# esp8266-01relayfabab-CONPLANOMASA.net
KiCad netlist of a schematic drawn in EAGLE
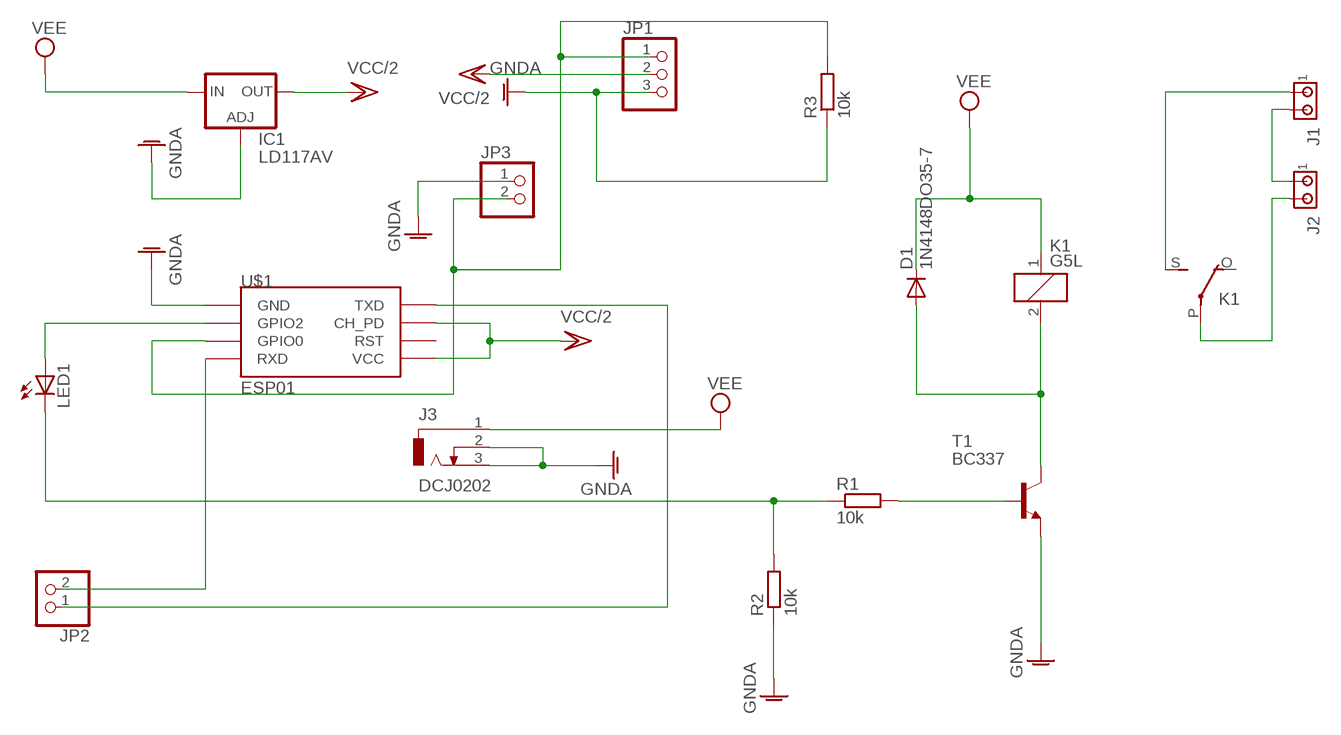
[diagram p0: schematic, sheet 1]

(export (version "E")
  (design (tool "Eeschema 10.0.6"))
  (components
    (comp (ref "D1")
      (value "1N4148DO35-7")
      (footprint "eagle-import:DO35-7")
      (libsource (lib "eagle-import") (part "1N4148DO35-7"))
    )
    (comp (ref "IC1")
      (value "LD117AV")
      (footprint "eagle-import:TO220L1")
      (libsource (lib "eagle-import") (part "LD117A?V"))
    )
    (comp (ref "J1")
      (value "MTA02-156")
      (footprint "eagle-import:1X2MTA")
      (libsource (lib "eagle-import") (part "MTA02-156"))
    )
    (comp (ref "J2")
      (value "MTA02-156")
      (footprint "eagle-import:1X2MTA")
      (libsource (lib "eagle-import") (part "MTA02-156"))
    )
    (comp (ref "J3")
      (value "DCJ0202")
      (footprint "eagle-import:DCJ0202")
      (libsource (lib "eagle-import") (part "DCJ0202"))
    )
    (comp (ref "JP1")
      (value "PINHD-1X3")
      (footprint "eagle-import:1X03")
      (libsource (lib "eagle-import") (part "PINHD-1X3"))
    )
    (comp (ref "JP2")
      (value "PINHD-1X2")
      (footprint "eagle-import:1X02")
      (libsource (lib "eagle-import") (part "PINHD-1X2"))
    )
    (comp (ref "JP3")
      (value "PINHD-1X2")
      (footprint "eagle-import:1X02")
      (libsource (lib "eagle-import") (part "PINHD-1X2"))
    )
    (comp (ref "K1")
      (value "G5L")
      (footprint "eagle-import:G5LE")
      (libsource (lib "eagle-import") (part "G5L"))
    )
    (comp (ref "LED1")
      (value "LED5MM")
      (footprint "eagle-import:LED5MM")
      (libsource (lib "eagle-import") (part "LED5MM"))
    )
    (comp (ref "R1")
      (value "10k")
      (footprint "eagle-import:0207_7")
      (libsource (lib "eagle-import") (part "R-EU_0207/7"))
    )
    (comp (ref "R2")
      (value "10k")
      (footprint "eagle-import:0207_7")
      (libsource (lib "eagle-import") (part "R-EU_0207/7"))
    )
    (comp (ref "R3")
      (value "10k")
      (footprint "eagle-import:0207_7")
      (libsource (lib "eagle-import") (part "R-EU_0207/7"))
    )
    (comp (ref "T1")
      (value "BC337")
      (footprint "eagle-import:TO92")
      (libsource (lib "eagle-import") (part "BC337"))
    )
    (comp (ref "U$1")
      (value "ESP01")
      (footprint "eagle-import:ESP01")
      (libsource (lib "eagle-import") (part "ESP01"))
    )
  )
  (nets
    (net (code "1") (name "GNDA") (class "Default")
      (node (ref "IC1") (pin "1") (pinfunction "ADJ_1") (pintype "input"))
      (node (ref "J3") (pin "2") (pinfunction "2_2") (pintype "passive"))
      (node (ref "J3") (pin "3") (pinfunction "3_3") (pintype "passive"))
      (node (ref "JP1") (pin "3") (pinfunction "3_3") (pintype "passive"))
      (node (ref "JP3") (pin "1") (pinfunction "1_1") (pintype "passive"))
      (node (ref "R2") (pin "1") (pinfunction "1_1") (pintype "passive"))
      (node (ref "R3") (pin "1") (pinfunction "1_1") (pintype "passive"))
      (node (ref "T1") (pin "1") (pinfunction "E_1") (pintype "passive"))
      (node (ref "U$1") (pin "GND") (pinfunction "GND_GND") (pintype "bidirectional"))
    )
    (net (code "2") (name "Net-(J1-Pad1)") (class "Default")
      (node (ref "J1") (pin "1") (pinfunction "1_1") (pintype "passive"))
      (node (ref "K1") (pin "S") (pinfunction "S_S") (pintype "passive"))
    )
    (net (code "3") (name "Net-(J1-Pad2)") (class "Default")
      (node (ref "J1") (pin "2") (pinfunction "2_2") (pintype "passive"))
      (node (ref "J2") (pin "1") (pinfunction "1_1") (pintype "passive"))
    )
    (net (code "4") (name "Net-(J2-Pad2)") (class "Default")
      (node (ref "J2") (pin "2") (pinfunction "2_2") (pintype "passive"))
      (node (ref "K1") (pin "P") (pinfunction "P_P") (pintype "passive"))
    )
    (net (code "5") (name "Net-(JP1-Pad1)") (class "Default")
      (node (ref "JP1") (pin "1") (pinfunction "1_1") (pintype "passive"))
      (node (ref "JP3") (pin "2") (pinfunction "2_2") (pintype "passive"))
      (node (ref "R3") (pin "2") (pinfunction "2_2") (pintype "passive"))
      (node (ref "U$1") (pin "GPIO0") (pinfunction "GPIO0_GPIO0") (pintype "bidirectional"))
    )
    (net (code "6") (name "Net-(LED1-C)") (class "Default")
      (node (ref "LED1") (pin "K") (pinfunction "C_K") (pintype "passive"))
      (node (ref "R1") (pin "1") (pinfunction "1_1") (pintype "passive"))
      (node (ref "R2") (pin "2") (pinfunction "2_2") (pintype "passive"))
    )
    (net (code "7") (name "Net-(LED1-PadA)") (class "Default")
      (node (ref "LED1") (pin "A") (pinfunction "A_A") (pintype "passive"))
      (node (ref "U$1") (pin "GPIO2") (pinfunction "GPIO2_GPIO2") (pintype "bidirectional"))
    )
    (net (code "8") (name "Net-(T1-B)") (class "Default")
      (node (ref "R1") (pin "2") (pinfunction "2_2") (pintype "passive"))
      (node (ref "T1") (pin "2") (pinfunction "B_2") (pintype "passive"))
    )
    (net (code "9") (name "Net-(T1-C)") (class "Default")
      (node (ref "D1") (pin "A") (pinfunction "A_A") (pintype "passive"))
      (node (ref "K1") (pin "2") (pinfunction "2_2") (pintype "passive"))
      (node (ref "T1") (pin "3") (pinfunction "C_3") (pintype "passive"))
    )
    (net (code "10") (name "Net-(U$1-RXD)") (class "Default")
      (node (ref "JP2") (pin "2") (pinfunction "2_2") (pintype "passive"))
      (node (ref "U$1") (pin "RX") (pinfunction "RXD_RX") (pintype "bidirectional"))
    )
    (net (code "11") (name "Net-(U$1-TXD)") (class "Default")
      (node (ref "JP2") (pin "1") (pinfunction "1_1") (pintype "passive"))
      (node (ref "U$1") (pin "TX") (pinfunction "TXD_TX") (pintype "bidirectional"))
    )
    (net (code "12") (name "VCC{slash}2") (class "Default")
      (node (ref "IC1") (pin "2") (pinfunction "OUT_2") (pintype "passive"))
      (node (ref "JP1") (pin "2") (pinfunction "2_2") (pintype "passive"))
      (node (ref "U$1") (pin "CH_PD") (pinfunction "CH_PD_CH_PD") (pintype "bidirectional"))
      (node (ref "U$1") (pin "VCC") (pinfunction "VCC_VCC") (pintype "bidirectional"))
    )
    (net (code "13") (name "VEE") (class "Default")
      (node (ref "D1") (pin "C") (pinfunction "C_C") (pintype "passive"))
      (node (ref "IC1") (pin "3") (pinfunction "IN_3") (pintype "input"))
      (node (ref "J3") (pin "1") (pinfunction "1_1") (pintype "passive"))
      (node (ref "K1") (pin "1") (pinfunction "1_1") (pintype "passive"))
    )
    (net (code "14") (name "unconnected-(K1-PadO)") (class "Default")
      (node (ref "K1") (pin "O") (pinfunction "O_O") (pintype "passive"))
    )
    (net (code "15") (name "unconnected-(U$1-PadRST)") (class "Default")
      (node (ref "U$1") (pin "RST") (pinfunction "RST_RST") (pintype "bidirectional"))
    )
  )
)
